# integrator.net
KiCad netlist of a schematic drawn in EAGLE
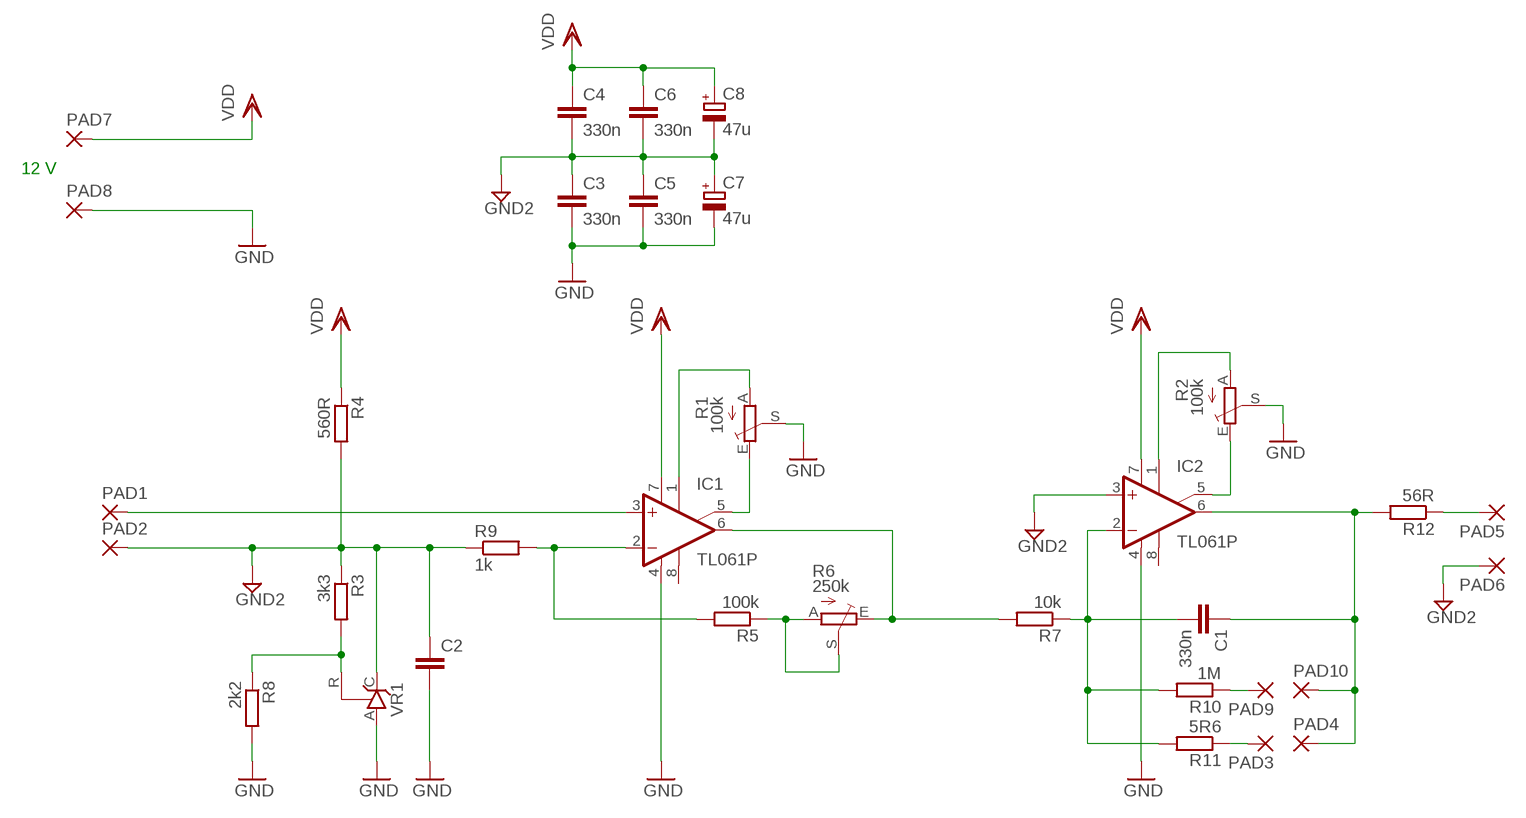
[diagram p0: schematic, sheet 1]

(export (version "E")
  (design (tool "Eeschema 10.0.6"))
  (components
    (comp (ref "C1")
      (value "330n")
      (footprint "eagle-import:C050-035X075")
      (libsource (lib "eagle-import") (part "C-EU050-035X075"))
    )
    (comp (ref "C2")
      (value "C-EU050-035X075")
      (footprint "eagle-import:C050-035X075")
      (libsource (lib "eagle-import") (part "C-EU050-035X075"))
    )
    (comp (ref "C3")
      (value "330n")
      (footprint "eagle-import:C050-035X075")
      (libsource (lib "eagle-import") (part "C-EU050-035X075"))
    )
    (comp (ref "C4")
      (value "330n")
      (footprint "eagle-import:C050-035X075")
      (libsource (lib "eagle-import") (part "C-EU050-035X075"))
    )
    (comp (ref "C5")
      (value "330n")
      (footprint "eagle-import:C050-035X075")
      (libsource (lib "eagle-import") (part "C-EU050-035X075"))
    )
    (comp (ref "C6")
      (value "330n")
      (footprint "eagle-import:C050-035X075")
      (libsource (lib "eagle-import") (part "C-EU050-035X075"))
    )
    (comp (ref "C7")
      (value "47u")
      (footprint "eagle-import:E2,5-7")
      (libsource (lib "eagle-import") (part "CPOL-EUE2.5-7"))
    )
    (comp (ref "C8")
      (value "47u")
      (footprint "eagle-import:E2,5-7")
      (libsource (lib "eagle-import") (part "CPOL-EUE2.5-7"))
    )
    (comp (ref "IC1")
      (value "TL061P")
      (footprint "eagle-import:DIL08")
      (libsource (lib "eagle-import") (part "TL061P"))
    )
    (comp (ref "IC2")
      (value "TL061P")
      (footprint "eagle-import:DIL08")
      (libsource (lib "eagle-import") (part "TL061P"))
    )
    (comp (ref "PAD1")
      (value "3,81/1,4")
      (footprint "eagle-import:3,81_1,4")
      (libsource (lib "eagle-import") (part "3,81/1,4"))
    )
    (comp (ref "PAD2")
      (value "3,81/1,4")
      (footprint "eagle-import:3,81_1,4")
      (libsource (lib "eagle-import") (part "3,81/1,4"))
    )
    (comp (ref "PAD3")
      (value "3,81/1,4")
      (footprint "eagle-import:3,81_1,4")
      (libsource (lib "eagle-import") (part "3,81/1,4"))
    )
    (comp (ref "PAD4")
      (value "3,81/1,4")
      (footprint "eagle-import:3,81_1,4")
      (libsource (lib "eagle-import") (part "3,81/1,4"))
    )
    (comp (ref "PAD5")
      (value "3,81/1,4")
      (footprint "eagle-import:3,81_1,4")
      (libsource (lib "eagle-import") (part "3,81/1,4"))
    )
    (comp (ref "PAD6")
      (value "3,81/1,4")
      (footprint "eagle-import:3,81_1,4")
      (libsource (lib "eagle-import") (part "3,81/1,4"))
    )
    (comp (ref "PAD7")
      (value "3,81/1,4")
      (footprint "eagle-import:3,81_1,4")
      (libsource (lib "eagle-import") (part "3,81/1,4"))
    )
    (comp (ref "PAD8")
      (value "3,81/1,4")
      (footprint "eagle-import:3,81_1,4")
      (libsource (lib "eagle-import") (part "3,81/1,4"))
    )
    (comp (ref "PAD9")
      (value "3,81/1,4")
      (footprint "eagle-import:3,81_1,4")
      (libsource (lib "eagle-import") (part "3,81/1,4"))
    )
    (comp (ref "PAD10")
      (value "3,81/1,4")
      (footprint "eagle-import:3,81_1,4")
      (libsource (lib "eagle-import") (part "3,81/1,4"))
    )
    (comp (ref "R1")
      (value "100k")
      (footprint "eagle-import:LI10")
      (libsource (lib "eagle-import") (part "TRIM_EU-LI10"))
    )
    (comp (ref "R2")
      (value "100k")
      (footprint "eagle-import:LI10")
      (libsource (lib "eagle-import") (part "TRIM_EU-LI10"))
    )
    (comp (ref "R3")
      (value "3k3")
      (footprint "eagle-import:0207_12")
      (libsource (lib "eagle-import") (part "R-EU_0207/12"))
    )
    (comp (ref "R4")
      (value "560R")
      (footprint "eagle-import:0207_12")
      (libsource (lib "eagle-import") (part "R-EU_0207/12"))
    )
    (comp (ref "R5")
      (value "100k")
      (footprint "eagle-import:0207_12")
      (libsource (lib "eagle-import") (part "R-EU_0207/12"))
    )
    (comp (ref "R6")
      (value "250k")
      (footprint "eagle-import:LI10")
      (libsource (lib "eagle-import") (part "TRIM_EU-LI10"))
    )
    (comp (ref "R7")
      (value "10k")
      (footprint "eagle-import:0207_12")
      (libsource (lib "eagle-import") (part "R-EU_0207/12"))
    )
    (comp (ref "R8")
      (value "2k2")
      (footprint "eagle-import:0207_12")
      (libsource (lib "eagle-import") (part "R-EU_0207/12"))
    )
    (comp (ref "R9")
      (value "1k")
      (footprint "eagle-import:0207_12")
      (libsource (lib "eagle-import") (part "R-EU_0207/12"))
    )
    (comp (ref "R10")
      (value "1M")
      (footprint "eagle-import:0207_12")
      (libsource (lib "eagle-import") (part "R-EU_0207/12"))
    )
    (comp (ref "R11")
      (value "5R6")
      (footprint "eagle-import:0207_12")
      (libsource (lib "eagle-import") (part "R-EU_0207/12"))
    )
    (comp (ref "R12")
      (value "56R")
      (footprint "eagle-import:0207_12")
      (libsource (lib "eagle-import") (part "R-EU_0207/12"))
    )
    (comp (ref "VR1")
      (value "TL431CLP")
      (footprint "eagle-import:TO92-CLP")
      (libsource (lib "eagle-import") (part "TL431CLP"))
    )
  )
  (nets
    (net (code "1") (name "GND") (class "Default")
      (node (ref "C2") (pin "2") (pinfunction "2_2") (pintype "passive"))
      (node (ref "C3") (pin "2") (pinfunction "2_2") (pintype "passive"))
      (node (ref "C5") (pin "2") (pinfunction "2_2") (pintype "passive"))
      (node (ref "C7") (pin "-") (pinfunction "-_-") (pintype "passive"))
      (node (ref "IC1") (pin "4") (pinfunction "V-_4") (pintype "power_in"))
      (node (ref "IC2") (pin "4") (pinfunction "V-_4") (pintype "power_in"))
      (node (ref "PAD8") (pin "1") (pinfunction "P_1") (pintype "passive"))
      (node (ref "R1") (pin "S") (pinfunction "S_S") (pintype "passive"))
      (node (ref "R2") (pin "S") (pinfunction "S_S") (pintype "passive"))
      (node (ref "R8") (pin "2") (pinfunction "2_2") (pintype "passive"))
      (node (ref "VR1") (pin "A") (pinfunction "A_A") (pintype "passive"))
    )
    (net (code "2") (name "GND2") (class "Default")
      (node (ref "C2") (pin "1") (pinfunction "1_1") (pintype "passive"))
      (node (ref "C3") (pin "1") (pinfunction "1_1") (pintype "passive"))
      (node (ref "C4") (pin "2") (pinfunction "2_2") (pintype "passive"))
      (node (ref "C5") (pin "1") (pinfunction "1_1") (pintype "passive"))
      (node (ref "C6") (pin "2") (pinfunction "2_2") (pintype "passive"))
      (node (ref "C7") (pin "+") (pinfunction "+_+") (pintype "passive"))
      (node (ref "C8") (pin "-") (pinfunction "-_-") (pintype "passive"))
      (node (ref "IC2") (pin "3") (pinfunction "+IN_3") (pintype "input"))
      (node (ref "PAD2") (pin "1") (pinfunction "P_1") (pintype "passive"))
      (node (ref "PAD6") (pin "1") (pinfunction "P_1") (pintype "passive"))
      (node (ref "R3") (pin "1") (pinfunction "1_1") (pintype "passive"))
      (node (ref "R4") (pin "2") (pinfunction "2_2") (pintype "passive"))
      (node (ref "R9") (pin "1") (pinfunction "1_1") (pintype "passive"))
      (node (ref "VR1") (pin "C") (pinfunction "C_C") (pintype "passive"))
    )
    (net (code "3") (name "Net-(IC1-+IN)") (class "Default")
      (node (ref "IC1") (pin "3") (pinfunction "+IN_3") (pintype "input"))
      (node (ref "PAD1") (pin "1") (pinfunction "P_1") (pintype "passive"))
    )
    (net (code "4") (name "Net-(IC1--IN)") (class "Default")
      (node (ref "IC1") (pin "2") (pinfunction "-IN_2") (pintype "input"))
      (node (ref "R5") (pin "2") (pinfunction "2_2") (pintype "passive"))
      (node (ref "R9") (pin "2") (pinfunction "2_2") (pintype "passive"))
    )
    (net (code "5") (name "Net-(IC1-ON1)") (class "Default")
      (node (ref "IC1") (pin "1") (pinfunction "ON1_1") (pintype "passive"))
      (node (ref "R1") (pin "A") (pinfunction "A_A") (pintype "passive"))
    )
    (net (code "6") (name "Net-(IC1-ON2)") (class "Default")
      (node (ref "IC1") (pin "5") (pinfunction "ON2_5") (pintype "passive"))
      (node (ref "R1") (pin "E") (pinfunction "E_E") (pintype "passive"))
    )
    (net (code "7") (name "Net-(IC1-OUT)") (class "Default")
      (node (ref "IC1") (pin "6") (pinfunction "OUT_6") (pintype "output"))
      (node (ref "R6") (pin "E") (pinfunction "E_E") (pintype "passive"))
      (node (ref "R7") (pin "2") (pinfunction "2_2") (pintype "passive"))
    )
    (net (code "8") (name "Net-(IC2--IN)") (class "Default")
      (node (ref "C1") (pin "2") (pinfunction "2_2") (pintype "passive"))
      (node (ref "IC2") (pin "2") (pinfunction "-IN_2") (pintype "input"))
      (node (ref "R10") (pin "2") (pinfunction "2_2") (pintype "passive"))
      (node (ref "R11") (pin "2") (pinfunction "2_2") (pintype "passive"))
      (node (ref "R7") (pin "1") (pinfunction "1_1") (pintype "passive"))
    )
    (net (code "9") (name "Net-(IC2-ON1)") (class "Default")
      (node (ref "IC2") (pin "1") (pinfunction "ON1_1") (pintype "passive"))
      (node (ref "R2") (pin "A") (pinfunction "A_A") (pintype "passive"))
    )
    (net (code "10") (name "Net-(IC2-ON2)") (class "Default")
      (node (ref "IC2") (pin "5") (pinfunction "ON2_5") (pintype "passive"))
      (node (ref "R2") (pin "E") (pinfunction "E_E") (pintype "passive"))
    )
    (net (code "11") (name "Net-(IC2-OUT)") (class "Default")
      (node (ref "C1") (pin "1") (pinfunction "1_1") (pintype "passive"))
      (node (ref "IC2") (pin "6") (pinfunction "OUT_6") (pintype "output"))
      (node (ref "PAD10") (pin "1") (pinfunction "P_1") (pintype "passive"))
      (node (ref "PAD4") (pin "1") (pinfunction "P_1") (pintype "passive"))
      (node (ref "R12") (pin "2") (pinfunction "2_2") (pintype "passive"))
    )
    (net (code "12") (name "Net-(PAD3-P)") (class "Default")
      (node (ref "PAD3") (pin "1") (pinfunction "P_1") (pintype "passive"))
      (node (ref "R11") (pin "1") (pinfunction "1_1") (pintype "passive"))
    )
    (net (code "13") (name "Net-(PAD5-P)") (class "Default")
      (node (ref "PAD5") (pin "1") (pinfunction "P_1") (pintype "passive"))
      (node (ref "R12") (pin "1") (pinfunction "1_1") (pintype "passive"))
    )
    (net (code "14") (name "Net-(PAD9-P)") (class "Default")
      (node (ref "PAD9") (pin "1") (pinfunction "P_1") (pintype "passive"))
      (node (ref "R10") (pin "1") (pinfunction "1_1") (pintype "passive"))
    )
    (net (code "15") (name "Net-(R3-Pad2)") (class "Default")
      (node (ref "R3") (pin "2") (pinfunction "2_2") (pintype "passive"))
      (node (ref "R8") (pin "1") (pinfunction "1_1") (pintype "passive"))
      (node (ref "VR1") (pin "R") (pinfunction "R_R") (pintype "passive"))
    )
    (net (code "16") (name "Net-(R5-Pad1)") (class "Default")
      (node (ref "R5") (pin "1") (pinfunction "1_1") (pintype "passive"))
      (node (ref "R6") (pin "A") (pinfunction "A_A") (pintype "passive"))
      (node (ref "R6") (pin "S") (pinfunction "S_S") (pintype "passive"))
    )
    (net (code "17") (name "VDD") (class "Default")
      (node (ref "C4") (pin "1") (pinfunction "1_1") (pintype "passive"))
      (node (ref "C6") (pin "1") (pinfunction "1_1") (pintype "passive"))
      (node (ref "C8") (pin "+") (pinfunction "+_+") (pintype "passive"))
      (node (ref "IC1") (pin "7") (pinfunction "V+_7") (pintype "power_in"))
      (node (ref "IC2") (pin "7") (pinfunction "V+_7") (pintype "power_in"))
      (node (ref "PAD7") (pin "1") (pinfunction "P_1") (pintype "passive"))
      (node (ref "R4") (pin "1") (pinfunction "1_1") (pintype "passive"))
    )
    (net (code "18") (name "unconnected-(IC1-OPT-Pad8)") (class "Default")
      (node (ref "IC1") (pin "8") (pinfunction "OPT_8") (pintype "passive"))
    )
    (net (code "19") (name "unconnected-(IC2-OPT-Pad8)") (class "Default")
      (node (ref "IC2") (pin "8") (pinfunction "OPT_8") (pintype "passive"))
    )
  )
)
